# PPG.net
KiCad netlist of a schematic drawn in Altium Designer
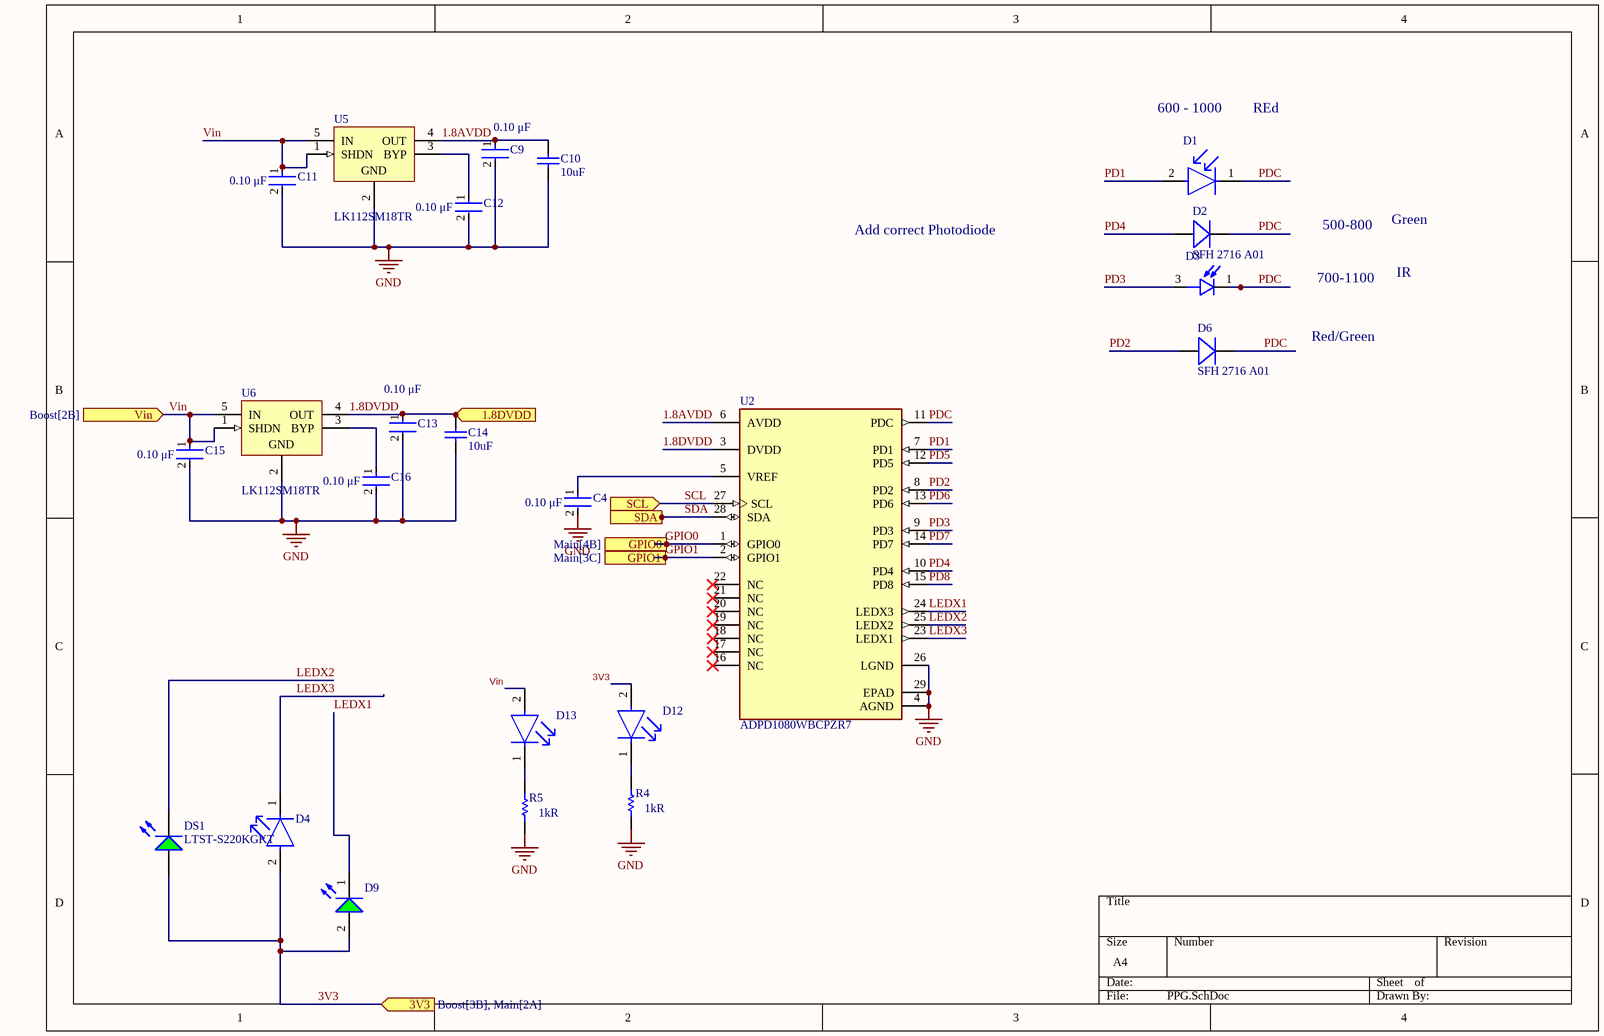
[diagram p0: PPG.SchDoc]

(export (version "E")
  (design (tool "Eeschema 10.0.6"))
  (components
    (comp (ref "C4")
      (value "C0402C104K3RACTU")
      (footprint "FP-C0402-BB-MFG")
      (description "Cap Ceramic 0.1uF 25V X7R 10% Pad SMD 0402 125C T/R")
      (fields
        (field (name "MANUFACTURER") "Kemet")
        (field (name "TOLERANCE") "0.1")
        (field (name "CAPACITANCE") "0.10 μF")
      )
      (libsource (lib "Altium Content Vault") (part "b4654b650e69147ec39a6b967a45e02"))
    )
    (comp (ref "C9")
      (value "C0402C104K3RACTU")
      (footprint "FP-C0402-BB-MFG")
      (description "Cap Ceramic 0.1uF 25V X7R 10% Pad SMD 0402 125C T/R")
      (fields
        (field (name "MANUFACTURER") "Kemet")
        (field (name "TOLERANCE") "0.1")
        (field (name "CAPACITANCE") "0.10 μF")
      )
      (libsource (lib "Altium Content Vault") (part "b4654b650e69147ec39a6b967a45e02"))
    )
    (comp (ref "C10")
      (value "10uF")
      (description "CL10 Series 0603 10 uF 16 V ±20% Tolerance X5R Multilayer Ceramic Chip Capacitor")
      (fields
        (field (name "MANUFACTURER") "Samsung")
        (field (name "MANUFACTURER PART NUMBER") "CL10A106MO8NQNC")
      )
      (libsource (lib "Simulation Generic Components") (part "Capacitor"))
    )
    (comp (ref "C11")
      (value "C0402C104K3RACTU")
      (footprint "FP-C0402-BB-MFG")
      (description "Cap Ceramic 0.1uF 25V X7R 10% Pad SMD 0402 125C T/R")
      (fields
        (field (name "MANUFACTURER") "Kemet")
        (field (name "TOLERANCE") "0.1")
        (field (name "CAPACITANCE") "0.10 μF")
      )
      (libsource (lib "Altium Content Vault") (part "b4654b650e69147ec39a6b967a45e02"))
    )
    (comp (ref "C12")
      (value "C0402C104K3RACTU")
      (footprint "FP-C0402-BB-MFG")
      (description "Cap Ceramic 0.1uF 25V X7R 10% Pad SMD 0402 125C T/R")
      (fields
        (field (name "MANUFACTURER") "Kemet")
        (field (name "TOLERANCE") "0.1")
        (field (name "CAPACITANCE") "0.10 μF")
      )
      (libsource (lib "Altium Content Vault") (part "b4654b650e69147ec39a6b967a45e02"))
    )
    (comp (ref "C13")
      (value "C0402C104K3RACTU")
      (footprint "FP-C0402-BB-MFG")
      (description "Cap Ceramic 0.1uF 25V X7R 10% Pad SMD 0402 125C T/R")
      (fields
        (field (name "MANUFACTURER") "Kemet")
        (field (name "TOLERANCE") "0.1")
        (field (name "CAPACITANCE") "0.10 μF")
      )
      (libsource (lib "Altium Content Vault") (part "b4654b650e69147ec39a6b967a45e02"))
    )
    (comp (ref "C14")
      (value "10uF")
      (description "CL10 Series 0603 10 uF 16 V ±20% Tolerance X5R Multilayer Ceramic Chip Capacitor")
      (fields
        (field (name "MANUFACTURER") "Samsung")
        (field (name "MANUFACTURER PART NUMBER") "CL10A106MO8NQNC")
      )
      (libsource (lib "Simulation Generic Components") (part "Capacitor"))
    )
    (comp (ref "C15")
      (value "C0402C104K3RACTU")
      (footprint "FP-C0402-BB-MFG")
      (description "Cap Ceramic 0.1uF 25V X7R 10% Pad SMD 0402 125C T/R")
      (fields
        (field (name "MANUFACTURER") "Kemet")
        (field (name "TOLERANCE") "0.1")
        (field (name "CAPACITANCE") "0.10 μF")
      )
      (libsource (lib "Altium Content Vault") (part "b4654b650e69147ec39a6b967a45e02"))
    )
    (comp (ref "C16")
      (value "C0402C104K3RACTU")
      (footprint "FP-C0402-BB-MFG")
      (description "Cap Ceramic 0.1uF 25V X7R 10% Pad SMD 0402 125C T/R")
      (fields
        (field (name "MANUFACTURER") "Kemet")
        (field (name "TOLERANCE") "0.1")
        (field (name "CAPACITANCE") "0.10 μF")
      )
      (libsource (lib "Altium Content Vault") (part "b4654b650e69147ec39a6b967a45e02"))
    )
    (comp (ref "D1")
      (value "SFH 2704")
      (footprint "FP-SFH_2704-MFG")
      (description "SENSOR PHOTODIODE 900NM 2SMD")
      (fields (field (name "MANUFACTURER") "Osram Opto"))
      (libsource (lib "Altium Content Vault") (part "9b7c99953c265a88c20b8f1023d9605"))
    )
    (comp (ref "D2")
      (value "SFH 2716 A01")
      (footprint "SFH 2716 A01")
      (description "Silicon PIN Photodiode with Vλ Characteristics, -40 to 100 °C, 1.3 x 2 x 0.8 mm")
      (fields (field (name "MANUFACTURER") "Osram Opto"))
      (libsource (lib "Schlib1") (part "SFH 2716 A01"))
    )
    (comp (ref "D3")
      (value "SFH 2400 FA")
      (footprint "SFH 2400 FA")
      (libsource (lib "Schlib1") (part "SFH 2400 FA"))
    )
    (comp (ref "D4")
      (value "LS R976-NR-1")
      (footprint "FP-LS_R976-MFG")
      (description "LED RED DIFFUSED 0805 SMD")
      (libsource (lib "Altium Content Vault") (part "8706943c75ba83719d021d2fdc84c58"))
    )
    (comp (ref "D6")
      (value "SFH 2716 A01")
      (footprint "SFH 2716 A01")
      (description "Silicon PIN Photodiode with Vλ Characteristics, -40 to 100 °C, 1.3 x 2 x 0.8 mm")
      (fields (field (name "MANUFACTURER") "Osram Opto"))
      (libsource (lib "Schlib1") (part "SFH 2716 A01"))
    )
    (comp (ref "D9")
      (value "150141GS73100")
      (footprint "WL-SMTW_3528")
      (fields (field (name "MANUFACTURER") "Wurth Electronics"))
      (libsource (lib "Altium Content Vault") (part "LED_Green_2A-1K"))
    )
    (comp (ref "D12")
      (value "LTST-S270KRKT")
      (footprint "FP-LTST-S270KRKT-MFG")
      (description "LED RED CLEAR CHIP SMD R/A")
      (fields (field (name "MANUFACTURER") "Vishay Lite-On"))
      (libsource (lib "Altium Content Vault") (part "8706943c75ba83719d021d2fdc84c58"))
    )
    (comp (ref "D13")
      (value "LTST-S270KRKT")
      (footprint "FP-LTST-S270KRKT-MFG")
      (description "LED RED CLEAR CHIP SMD R/A")
      (fields (field (name "MANUFACTURER") "Vishay Lite-On"))
      (libsource (lib "Altium Content Vault") (part "8706943c75ba83719d021d2fdc84c58"))
    )
    (comp (ref "DS1")
      (value "LTST-S220KGKT")
      (footprint "LTST-S220KGKT_V")
      (description "LED Green, 75 mW, 30 mA, -30 to 85 degC, 2-Pin SMD, RoHS, Tape and Reel")
      (fields (field (name "MANUFACTURER") "Lite-On"))
      (libsource (lib "Altium Content Vault") (part "LED-GREEN-AK-2"))
    )
    (comp (ref "R4")
      (value "1kR")
      (footprint "RESC1005X40X25LL10T10")
      (fields
        (field (name "PART NUMBER") "RK73H1ETTP1001F")
        (field (name "MANUFACTURER") "KOA Speer")
        (field (name "TOLERANCE") "1%")
      )
      (libsource (lib "Altium Content Vault") (part "RES"))
    )
    (comp (ref "R5")
      (value "1kR")
      (footprint "RESC1005X40X25LL10T10")
      (fields
        (field (name "PART NUMBER") "RK73H1ETTP1001F")
        (field (name "MANUFACTURER") "KOA Speer")
        (field (name "TOLERANCE") "1%")
      )
      (libsource (lib "Altium Content Vault") (part "RES"))
    )
    (comp (ref "U2")
      (value "ADPD1080WBCPZR7")
      (footprint "ADPD1080WBCPZR7")
      (description "Optical Afe For Health Monitorin")
      (libsource (lib "Schlib1") (part "ADPD1080WBCPZR7"))
    )
    (comp (ref "U5")
      (value "LK112SM18TR")
      (footprint "SOT23-5L_M")
      (fields (field (name "MANUFACTURER") "STMicroelectronics"))
      (libsource (lib "Altium Content Vault") (part "PM-REG-LK112M-SOT5"))
    )
    (comp (ref "U6")
      (value "LK112SM18TR")
      (footprint "SOT23-5L_M")
      (fields (field (name "MANUFACTURER") "STMicroelectronics"))
      (libsource (lib "Altium Content Vault") (part "PM-REG-LK112M-SOT5"))
    )
  )
  (nets
    (net (code "1") (name "/1.8AVDD") (class "Default")
      (node (ref "C10") (pin "2") (pinfunction "2_2") (pintype "passive"))
      (node (ref "C9") (pin "1") (pinfunction "1_1") (pintype "passive"))
      (node (ref "U2") (pin "6") (pinfunction "AVDD_6") (pintype "power_in"))
      (node (ref "U5") (pin "4") (pinfunction "OUT_4") (pintype "power_in"))
    )
    (net (code "2") (name "/1.8DVDD") (class "Default")
      (node (ref "C13") (pin "1") (pinfunction "1_1") (pintype "passive"))
      (node (ref "C14") (pin "2") (pinfunction "2_2") (pintype "passive"))
      (node (ref "U2") (pin "3") (pinfunction "DVDD_3") (pintype "power_in"))
      (node (ref "U6") (pin "4") (pinfunction "OUT_4") (pintype "power_in"))
    )
    (net (code "3") (name "/3V3") (class "Default")
      (node (ref "D12") (pin "2") (pinfunction "A_2") (pintype "passive"))
      (node (ref "D4") (pin "2") (pinfunction "A_2") (pintype "passive"))
      (node (ref "D9") (pin "2") (pinfunction "A_2") (pintype "passive"))
      (node (ref "DS1") (pin "1") (pinfunction "A_1") (pintype "passive"))
    )
    (net (code "4") (name "/GPIO0") (class "Default")
      (node (ref "U2") (pin "1") (pinfunction "GPIO0_1") (pintype "bidirectional"))
    )
    (net (code "5") (name "/GPIO1") (class "Default")
      (node (ref "U2") (pin "2") (pinfunction "GPIO1_2") (pintype "bidirectional"))
    )
    (net (code "6") (name "/LEDX1") (class "Default")
      (node (ref "D9") (pin "1") (pinfunction "K_1") (pintype "passive"))
      (node (ref "U2") (pin "24") (pinfunction "LEDX3_24") (pintype "output"))
    )
    (net (code "7") (name "/LEDX2") (class "Default")
      (node (ref "DS1") (pin "2") (pinfunction "K_2") (pintype "passive"))
      (node (ref "U2") (pin "25") (pinfunction "LEDX2_25") (pintype "output"))
    )
    (net (code "8") (name "/LEDX3") (class "Default")
      (node (ref "D4") (pin "1") (pinfunction "C_1") (pintype "passive"))
      (node (ref "U2") (pin "23") (pinfunction "LEDX1_23") (pintype "output"))
    )
    (net (code "9") (name "/PD1") (class "Default")
      (node (ref "D1") (pin "2") (pinfunction "A_2") (pintype "passive"))
      (node (ref "U2") (pin "7") (pinfunction "PD1_7") (pintype "input"))
    )
    (net (code "10") (name "/PD2") (class "Default")
      (node (ref "D6") (pin "A") (pinfunction "A_A") (pintype "passive"))
      (node (ref "U2") (pin "8") (pinfunction "PD2_8") (pintype "input"))
    )
    (net (code "11") (name "/PD3") (class "Default")
      (node (ref "D3") (pin "3") (pinfunction "A_3") (pintype "passive"))
      (node (ref "U2") (pin "9") (pinfunction "PD3_9") (pintype "input"))
    )
    (net (code "12") (name "/PD4") (class "Default")
      (node (ref "D2") (pin "A") (pinfunction "A_A") (pintype "passive"))
      (node (ref "U2") (pin "10") (pinfunction "PD4_10") (pintype "input"))
    )
    (net (code "13") (name "/PD5") (class "Default")
      (node (ref "U2") (pin "12") (pinfunction "PD5_12") (pintype "input"))
    )
    (net (code "14") (name "/PD6") (class "Default")
      (node (ref "U2") (pin "13") (pinfunction "PD6_13") (pintype "input"))
    )
    (net (code "15") (name "/PD7") (class "Default")
      (node (ref "U2") (pin "14") (pinfunction "PD7_14") (pintype "input"))
    )
    (net (code "16") (name "/PD8") (class "Default")
      (node (ref "U2") (pin "15") (pinfunction "PD8_15") (pintype "input"))
    )
    (net (code "17") (name "/PDC") (class "Default")
      (node (ref "D1") (pin "1") (pinfunction "C_1") (pintype "passive"))
      (node (ref "D2") (pin "K") (pinfunction "K_K") (pintype "passive"))
      (node (ref "D3") (pin "1") (pinfunction "C_1") (pintype "passive"))
      (node (ref "D6") (pin "K") (pinfunction "K_K") (pintype "passive"))
      (node (ref "U2") (pin "11") (pinfunction "PDC_11") (pintype "output"))
    )
    (net (code "18") (name "/SCL") (class "Default")
      (node (ref "U2") (pin "27") (pinfunction "SCL_27") (pintype "input"))
    )
    (net (code "19") (name "/SDA") (class "Default")
      (node (ref "U2") (pin "28") (pinfunction "SDA_28") (pintype "bidirectional"))
    )
    (net (code "20") (name "/Vin") (class "Default")
      (node (ref "C11") (pin "1") (pinfunction "1_1") (pintype "passive"))
      (node (ref "C15") (pin "1") (pinfunction "1_1") (pintype "passive"))
      (node (ref "D13") (pin "2") (pinfunction "A_2") (pintype "passive"))
      (node (ref "U5") (pin "1") (pinfunction "SHDN_1") (pintype "input"))
      (node (ref "U5") (pin "5") (pinfunction "IN_5") (pintype "power_in"))
      (node (ref "U6") (pin "1") (pinfunction "SHDN_1") (pintype "input"))
      (node (ref "U6") (pin "5") (pinfunction "IN_5") (pintype "power_in"))
    )
    (net (code "21") (name "GND") (class "Default")
      (node (ref "C10") (pin "1") (pinfunction "1_1") (pintype "passive"))
      (node (ref "C11") (pin "2") (pinfunction "2_2") (pintype "passive"))
      (node (ref "C12") (pin "2") (pinfunction "2_2") (pintype "passive"))
      (node (ref "C13") (pin "2") (pinfunction "2_2") (pintype "passive"))
      (node (ref "C14") (pin "1") (pinfunction "1_1") (pintype "passive"))
      (node (ref "C15") (pin "2") (pinfunction "2_2") (pintype "passive"))
      (node (ref "C16") (pin "2") (pinfunction "2_2") (pintype "passive"))
      (node (ref "C4") (pin "2") (pinfunction "2_2") (pintype "passive"))
      (node (ref "C9") (pin "2") (pinfunction "2_2") (pintype "passive"))
      (node (ref "R4") (pin "1") (pinfunction "1_1") (pintype "passive"))
      (node (ref "R5") (pin "1") (pinfunction "1_1") (pintype "passive"))
      (node (ref "U2") (pin "26") (pinfunction "LGND_26") (pintype "power_in"))
      (node (ref "U2") (pin "29") (pinfunction "EPAD_29") (pintype "passive"))
      (node (ref "U2") (pin "4") (pinfunction "AGND_4") (pintype "power_in"))
      (node (ref "U5") (pin "2") (pinfunction "GND_2") (pintype "power_in"))
      (node (ref "U6") (pin "2") (pinfunction "GND_2") (pintype "power_in"))
    )
    (net (code "22") (name "Net-(D12-C)") (class "Default")
      (node (ref "D12") (pin "1") (pinfunction "C_1") (pintype "passive"))
      (node (ref "R4") (pin "2") (pinfunction "2_2") (pintype "passive"))
    )
    (net (code "23") (name "Net-(D13-C)") (class "Default")
      (node (ref "D13") (pin "1") (pinfunction "C_1") (pintype "passive"))
      (node (ref "R5") (pin "2") (pinfunction "2_2") (pintype "passive"))
    )
    (net (code "24") (name "Net-(U2-VREF)") (class "Default")
      (node (ref "C4") (pin "1") (pinfunction "1_1") (pintype "passive"))
      (node (ref "U2") (pin "5") (pinfunction "VREF_5") (pintype "passive"))
    )
    (net (code "25") (name "Net-(U5-BYP)") (class "Default")
      (node (ref "C12") (pin "1") (pinfunction "1_1") (pintype "passive"))
      (node (ref "U5") (pin "3") (pinfunction "BYP_3") (pintype "passive"))
    )
    (net (code "26") (name "Net-(U6-BYP)") (class "Default")
      (node (ref "C16") (pin "1") (pinfunction "1_1") (pintype "passive"))
      (node (ref "U6") (pin "3") (pinfunction "BYP_3") (pintype "passive"))
    )
    (net (code "27") (name "unconnected-(U2-NC-Pad16)") (class "Default")
      (node (ref "U2") (pin "16") (pinfunction "NC_16") (pintype "passive+no_connect"))
    )
    (net (code "28") (name "unconnected-(U2-NC-Pad17)") (class "Default")
      (node (ref "U2") (pin "17") (pinfunction "NC_17") (pintype "passive+no_connect"))
    )
    (net (code "29") (name "unconnected-(U2-NC-Pad18)") (class "Default")
      (node (ref "U2") (pin "18") (pinfunction "NC_18") (pintype "passive+no_connect"))
    )
    (net (code "30") (name "unconnected-(U2-NC-Pad19)") (class "Default")
      (node (ref "U2") (pin "19") (pinfunction "NC_19") (pintype "passive+no_connect"))
    )
    (net (code "31") (name "unconnected-(U2-NC-Pad20)") (class "Default")
      (node (ref "U2") (pin "20") (pinfunction "NC_20") (pintype "passive+no_connect"))
    )
    (net (code "32") (name "unconnected-(U2-NC-Pad21)") (class "Default")
      (node (ref "U2") (pin "21") (pinfunction "NC_21") (pintype "passive+no_connect"))
    )
    (net (code "33") (name "unconnected-(U2-NC-Pad22)") (class "Default")
      (node (ref "U2") (pin "22") (pinfunction "NC_22") (pintype "passive+no_connect"))
    )
  )
)
